# TrakerS_onecznyV3.net
KiCad netlist of a schematic drawn in EAGLE
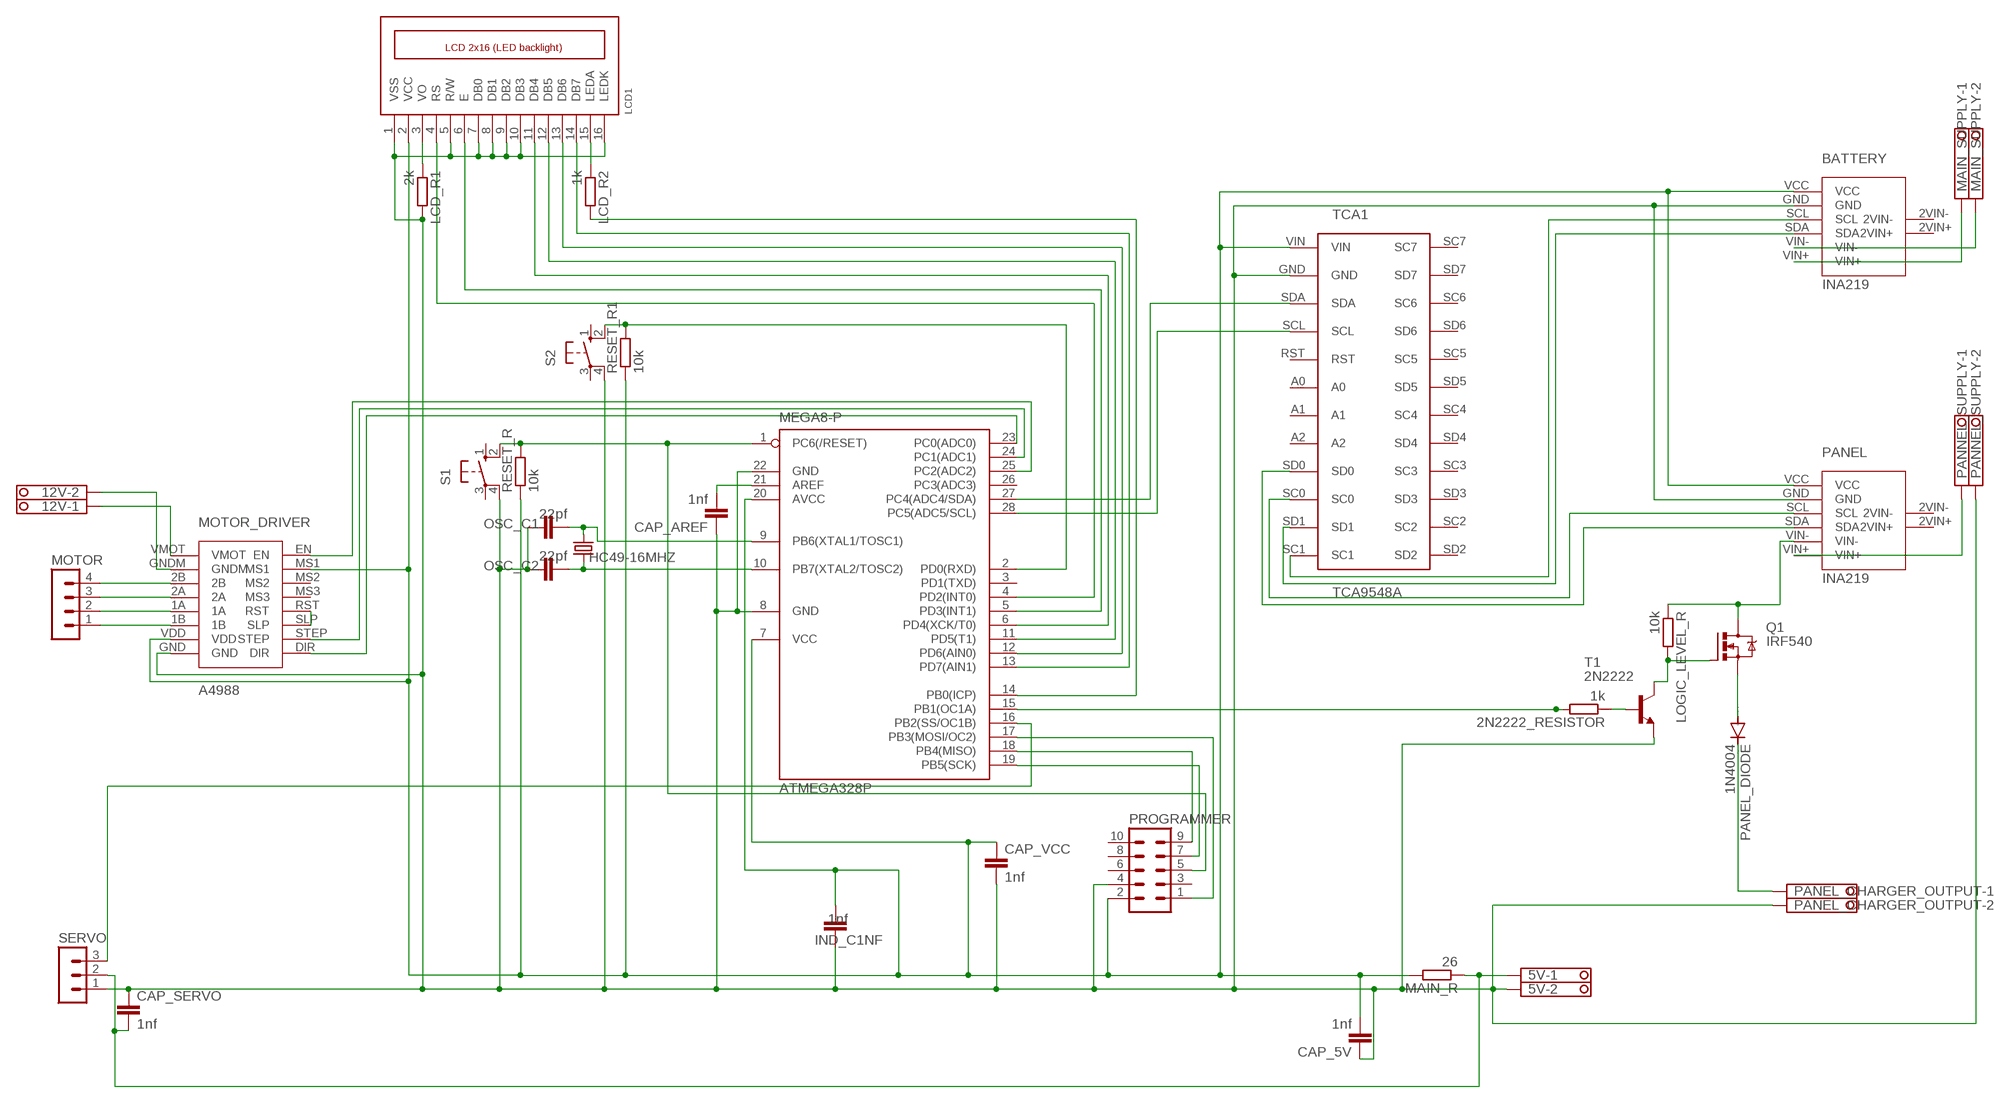
[diagram p0: schematic, sheet 1]

(export (version "E")
  (design (tool "Eeschema 10.0.6"))
  (components
    (comp (ref "2N2222_RESISTOR")
      (value "1k")
      (footprint "eagle-import:0207_2V")
      (libsource (lib "eagle-import") (part "R-EU_0207/2V"))
    )
    (comp (ref "5V")
      (value "TERMINAL-BLOCK-3.5MM-2-PIN-ROUND-PAD")
      (footprint "eagle-import:TERMINAL-BLOCK-2-PIN-3.5MM-ROUND-PAD")
      (libsource (lib "eagle-import") (part "TERMINAL-BLOCK-3.5MM-2-PIN-ROUND-PAD"))
    )
    (comp (ref "12V")
      (value "TERMINAL-BLOCK-3.5MM-2-PIN-ROUND-PAD")
      (footprint "eagle-import:TERMINAL-BLOCK-2-PIN-3.5MM-ROUND-PAD")
      (libsource (lib "eagle-import") (part "TERMINAL-BLOCK-3.5MM-2-PIN-ROUND-PAD"))
    )
    (comp (ref "ATMEGA328P")
      (value "MEGA8-P")
      (footprint "eagle-import:DIL28-3")
      (libsource (lib "eagle-import") (part "MEGA8-P"))
    )
    (comp (ref "BATTERY")
      (value "INA219")
      (footprint "eagle-import:INA219")
      (libsource (lib "eagle-import") (part "INA219"))
    )
    (comp (ref "CAP_5V")
      (value "1nf")
      (footprint "eagle-import:C025-024X044")
      (libsource (lib "eagle-import") (part "C-EU025-024X044"))
    )
    (comp (ref "CAP_AREF")
      (value "1nf")
      (footprint "eagle-import:C025-024X044")
      (libsource (lib "eagle-import") (part "C-EU025-024X044"))
    )
    (comp (ref "CAP_SERVO")
      (value "1nf")
      (footprint "eagle-import:C025-024X044")
      (libsource (lib "eagle-import") (part "C-EU025-024X044"))
    )
    (comp (ref "CAP_VCC")
      (value "1nf")
      (footprint "eagle-import:C025-024X044")
      (libsource (lib "eagle-import") (part "C-EU025-024X044"))
    )
    (comp (ref "HC49-16MHZ")
      (value "CRYTALHC49S")
      (footprint "eagle-import:HC49_S")
      (libsource (lib "eagle-import") (part "CRYTALHC49S"))
    )
    (comp (ref "IND_C1NF")
      (value "1nf")
      (footprint "eagle-import:C025-024X044")
      (libsource (lib "eagle-import") (part "C-EU025-024X044"))
    )
    (comp (ref "LCD1")
      (value "LCD_2X16_SIL")
      (footprint "eagle-import:HY-1602F")
      (libsource (lib "eagle-import") (part "LCD_2X16_SIL"))
    )
    (comp (ref "LCD_R1")
      (value "2k")
      (footprint "eagle-import:0207_2V")
      (libsource (lib "eagle-import") (part "R-EU_0207/2V"))
    )
    (comp (ref "LCD_R2")
      (value "1k")
      (footprint "eagle-import:0207_2V")
      (libsource (lib "eagle-import") (part "R-EU_0207/2V"))
    )
    (comp (ref "LOGIC_LEVEL_R")
      (value "10k")
      (footprint "eagle-import:0207_2V")
      (libsource (lib "eagle-import") (part "R-EU_0207/2V"))
    )
    (comp (ref "MAIN_R")
      (value "26")
      (footprint "eagle-import:0207_2V")
      (libsource (lib "eagle-import") (part "R-EU_0207/2V"))
    )
    (comp (ref "MAIN_SUPPLY")
      (value "TERMINAL-BLOCK-3.5MM-2-PIN-ROUND-PAD")
      (footprint "eagle-import:TERMINAL-BLOCK-2-PIN-3.5MM-ROUND-PAD")
      (libsource (lib "eagle-import") (part "TERMINAL-BLOCK-3.5MM-2-PIN-ROUND-PAD"))
    )
    (comp (ref "MOTOR")
      (value "MA04-1")
      (footprint "eagle-import:MA04-1")
      (libsource (lib "eagle-import") (part "MA04-1"))
    )
    (comp (ref "MOTOR_DRIVER")
      (value "A4988")
      (footprint "eagle-import:A4988")
      (libsource (lib "eagle-import") (part "A4988"))
    )
    (comp (ref "OSC_C1")
      (value "22pf")
      (footprint "eagle-import:C025-024X044")
      (libsource (lib "eagle-import") (part "C-EU025-024X044"))
    )
    (comp (ref "OSC_C2")
      (value "22pf")
      (footprint "eagle-import:C025-024X044")
      (libsource (lib "eagle-import") (part "C-EU025-024X044"))
    )
    (comp (ref "PANEL")
      (value "INA219")
      (footprint "eagle-import:INA219")
      (libsource (lib "eagle-import") (part "INA219"))
    )
    (comp (ref "PANEL_CHARGER_OUTPUT")
      (value "TERMINAL-BLOCK-3.5MM-2-PIN-ROUND-PAD")
      (footprint "eagle-import:TERMINAL-BLOCK-2-PIN-3.5MM-ROUND-PAD")
      (libsource (lib "eagle-import") (part "TERMINAL-BLOCK-3.5MM-2-PIN-ROUND-PAD"))
    )
    (comp (ref "PANEL_DIODE")
      (value "1N4004")
      (footprint "eagle-import:DO41-10")
      (libsource (lib "eagle-import") (part "1N4004"))
    )
    (comp (ref "PANNEL_SUPPLY")
      (value "TERMINAL-BLOCK-3.5MM-2-PIN-ROUND-PAD")
      (footprint "eagle-import:TERMINAL-BLOCK-2-PIN-3.5MM-ROUND-PAD")
      (libsource (lib "eagle-import") (part "TERMINAL-BLOCK-3.5MM-2-PIN-ROUND-PAD"))
    )
    (comp (ref "PROGRAMMER")
      (value "MA05-2")
      (footprint "eagle-import:MA05-2")
      (libsource (lib "eagle-import") (part "MA05-2"))
    )
    (comp (ref "Q1")
      (value "IRF540")
      (footprint "eagle-import:TO220BV")
      (libsource (lib "eagle-import") (part "IRF540"))
    )
    (comp (ref "RESET_R")
      (value "10k")
      (footprint "eagle-import:0207_2V")
      (libsource (lib "eagle-import") (part "R-EU_0207/2V"))
    )
    (comp (ref "RESET_R1")
      (value "10k")
      (footprint "eagle-import:0207_2V")
      (libsource (lib "eagle-import") (part "R-EU_0207/2V"))
    )
    (comp (ref "S1")
      (value "10-XX")
      (footprint "eagle-import:B3F-10XX")
      (fields (field (name "MPN") "B3F-1000"))
      (libsource (lib "eagle-import") (part "10-XX"))
    )
    (comp (ref "S2")
      (value "10-XX")
      (footprint "eagle-import:B3F-10XX")
      (fields (field (name "MPN") "B3F-1000"))
      (libsource (lib "eagle-import") (part "10-XX"))
    )
    (comp (ref "SERVO")
      (value "MA03-1")
      (footprint "eagle-import:MA03-1")
      (libsource (lib "eagle-import") (part "MA03-1"))
    )
    (comp (ref "T1")
      (value "2N2222")
      (footprint "eagle-import:TO92-EBC-OVAL")
      (libsource (lib "eagle-import") (part "2N2222"))
    )
    (comp (ref "TCA1")
      (value "TCA9548A")
      (footprint "eagle-import:TCA9548A")
      (libsource (lib "eagle-import") (part "TCA9548A"))
    )
  )
  (nets
    (net (code "1") (name "Net-(2N2222_RESISTOR-Pad1)") (class "Default")
      (node (ref "2N2222_RESISTOR") (pin "1") (pinfunction "1_1") (pintype "passive"))
      (node (ref "T1") (pin "B") (pinfunction "B_B") (pintype "passive"))
    )
    (net (code "2") (name "Net-(5VA-K)") (class "Default")
      (node (ref "5V") (pin "1") (pinfunction "K_1") (pintype "passive"))
      (node (ref "CAP_SERVO") (pin "2") (pinfunction "2_2") (pintype "passive"))
      (node (ref "MAIN_R") (pin "1") (pinfunction "1_1") (pintype "passive"))
      (node (ref "SERVO") (pin "2") (pinfunction "2_2") (pintype "passive"))
    )
    (net (code "3") (name "Net-(5VB-K)") (class "Default")
      (node (ref "5V") (pin "2") (pinfunction "K_2") (pintype "passive"))
      (node (ref "ATMEGA328P") (pin "22") (pinfunction "GND_22") (pintype "power_in"))
      (node (ref "ATMEGA328P") (pin "8") (pinfunction "GND_8") (pintype "power_in"))
      (node (ref "BATTERY") (pin "GND") (pinfunction "GND_GND") (pintype "bidirectional"))
      (node (ref "CAP_5V") (pin "1") (pinfunction "1_1") (pintype "passive"))
      (node (ref "CAP_AREF") (pin "1") (pinfunction "1_1") (pintype "passive"))
      (node (ref "CAP_SERVO") (pin "1") (pinfunction "1_1") (pintype "passive"))
      (node (ref "CAP_VCC") (pin "2") (pinfunction "2_2") (pintype "passive"))
      (node (ref "IND_C1NF") (pin "1") (pinfunction "1_1") (pintype "passive"))
      (node (ref "LCD1") (pin "1") (pinfunction "VSS_1") (pintype "power_in"))
      (node (ref "LCD1") (pin "10") (pinfunction "DB3_10") (pintype "bidirectional"))
      (node (ref "LCD1") (pin "16") (pinfunction "LEDK_16") (pintype "passive"))
      (node (ref "LCD1") (pin "5") (pinfunction "R/W_5") (pintype "input"))
      (node (ref "LCD1") (pin "7") (pinfunction "DB0_7") (pintype "bidirectional"))
      (node (ref "LCD1") (pin "8") (pinfunction "DB1_8") (pintype "bidirectional"))
      (node (ref "LCD1") (pin "9") (pinfunction "DB2_9") (pintype "bidirectional"))
      (node (ref "LCD_R1") (pin "2") (pinfunction "2_2") (pintype "passive"))
      (node (ref "MOTOR_DRIVER") (pin "GND") (pinfunction "GND_GND") (pintype "bidirectional"))
      (node (ref "OSC_C1") (pin "1") (pinfunction "1_1") (pintype "passive"))
      (node (ref "OSC_C2") (pin "1") (pinfunction "1_1") (pintype "passive"))
      (node (ref "PANEL") (pin "GND") (pinfunction "GND_GND") (pintype "bidirectional"))
      (node (ref "PANEL_CHARGER_OUTPUT") (pin "2") (pinfunction "K_2") (pintype "passive"))
      (node (ref "PANNEL_SUPPLY") (pin "2") (pinfunction "K_2") (pintype "passive"))
      (node (ref "PROGRAMMER") (pin "4") (pinfunction "4_4") (pintype "passive"))
      (node (ref "S1") (pin "4") (pinfunction "P1_4") (pintype "passive"))
      (node (ref "S2") (pin "4") (pinfunction "P1_4") (pintype "passive"))
      (node (ref "SERVO") (pin "1") (pinfunction "1_1") (pintype "passive"))
      (node (ref "T1") (pin "E") (pinfunction "E_E") (pintype "passive"))
      (node (ref "TCA1") (pin "GND") (pinfunction "GND_GND") (pintype "bidirectional"))
    )
    (net (code "4") (name "Net-(12VA-K)") (class "Default")
      (node (ref "12V") (pin "1") (pinfunction "K_1") (pintype "passive"))
      (node (ref "MOTOR_DRIVER") (pin "VMOT") (pinfunction "VMOT_VMOT") (pintype "bidirectional"))
    )
    (net (code "5") (name "Net-(12VB-K)") (class "Default")
      (node (ref "12V") (pin "2") (pinfunction "K_2") (pintype "passive"))
      (node (ref "MOTOR_DRIVER") (pin "GNDM") (pinfunction "GNDM_GNDM") (pintype "bidirectional"))
    )
    (net (code "6") (name "Net-(ATMEGA328P-AREF)") (class "Default")
      (node (ref "ATMEGA328P") (pin "21") (pinfunction "AREF_21") (pintype "passive"))
      (node (ref "CAP_AREF") (pin "2") (pinfunction "2_2") (pintype "passive"))
    )
    (net (code "7") (name "Net-(ATMEGA328P-AVCC)") (class "Default")
      (node (ref "ATMEGA328P") (pin "20") (pinfunction "AVCC_20") (pintype "power_in"))
      (node (ref "ATMEGA328P") (pin "7") (pinfunction "VCC_7") (pintype "power_in"))
      (node (ref "BATTERY") (pin "VCC") (pinfunction "VCC_VCC") (pintype "bidirectional"))
      (node (ref "CAP_5V") (pin "2") (pinfunction "2_2") (pintype "passive"))
      (node (ref "CAP_VCC") (pin "1") (pinfunction "1_1") (pintype "passive"))
      (node (ref "IND_C1NF") (pin "2") (pinfunction "2_2") (pintype "passive"))
      (node (ref "LCD1") (pin "2") (pinfunction "VCC_2") (pintype "power_in"))
      (node (ref "MAIN_R") (pin "2") (pinfunction "2_2") (pintype "passive"))
      (node (ref "MOTOR_DRIVER") (pin "MS1") (pinfunction "MS1_MS1") (pintype "bidirectional"))
      (node (ref "MOTOR_DRIVER") (pin "VDD") (pinfunction "VDD_VDD") (pintype "bidirectional"))
      (node (ref "PANEL") (pin "VCC") (pinfunction "VCC_VCC") (pintype "bidirectional"))
      (node (ref "PROGRAMMER") (pin "2") (pinfunction "2_2") (pintype "passive"))
      (node (ref "RESET_R") (pin "1") (pinfunction "1_1") (pintype "passive"))
      (node (ref "RESET_R1") (pin "1") (pinfunction "1_1") (pintype "passive"))
      (node (ref "TCA1") (pin "VIN") (pinfunction "VIN_VIN") (pintype "bidirectional"))
    )
    (net (code "8") (name "Net-(ATMEGA328P-PB0(ICP))") (class "Default")
      (node (ref "ATMEGA328P") (pin "14") (pinfunction "PB0(ICP)_14") (pintype "bidirectional"))
      (node (ref "LCD_R2") (pin "2") (pinfunction "2_2") (pintype "passive"))
    )
    (net (code "9") (name "Net-(ATMEGA328P-PB1(OC1A))") (class "Default")
      (node (ref "2N2222_RESISTOR") (pin "2") (pinfunction "2_2") (pintype "passive"))
      (node (ref "ATMEGA328P") (pin "15") (pinfunction "PB1(OC1A)_15") (pintype "bidirectional"))
    )
    (net (code "10") (name "Net-(ATMEGA328P-PB2(SS{slash}OC1B))") (class "Default")
      (node (ref "ATMEGA328P") (pin "16") (pinfunction "PB2(SS/OC1B)_16") (pintype "bidirectional"))
      (node (ref "SERVO") (pin "3") (pinfunction "3_3") (pintype "passive"))
    )
    (net (code "11") (name "Net-(ATMEGA328P-PB3(MOSI{slash}OC2))") (class "Default")
      (node (ref "ATMEGA328P") (pin "17") (pinfunction "PB3(MOSI/OC2)_17") (pintype "bidirectional"))
      (node (ref "PROGRAMMER") (pin "1") (pinfunction "1_1") (pintype "passive"))
    )
    (net (code "12") (name "Net-(ATMEGA328P-PB4(MISO))") (class "Default")
      (node (ref "ATMEGA328P") (pin "18") (pinfunction "PB4(MISO)_18") (pintype "bidirectional"))
      (node (ref "PROGRAMMER") (pin "9") (pinfunction "9_9") (pintype "passive"))
    )
    (net (code "13") (name "Net-(ATMEGA328P-PB5(SCK))") (class "Default")
      (node (ref "ATMEGA328P") (pin "19") (pinfunction "PB5(SCK)_19") (pintype "bidirectional"))
      (node (ref "PROGRAMMER") (pin "7") (pinfunction "7_7") (pintype "passive"))
    )
    (net (code "14") (name "Net-(ATMEGA328P-PB6(XTAL1{slash}TOSC1))") (class "Default")
      (node (ref "ATMEGA328P") (pin "9") (pinfunction "PB6(XTAL1/TOSC1)_9") (pintype "bidirectional"))
      (node (ref "HC49-16MHZ") (pin "1") (pinfunction "1_1") (pintype "passive"))
      (node (ref "OSC_C1") (pin "2") (pinfunction "2_2") (pintype "passive"))
    )
    (net (code "15") (name "Net-(ATMEGA328P-PB7(XTAL2{slash}TOSC2))") (class "Default")
      (node (ref "ATMEGA328P") (pin "10") (pinfunction "PB7(XTAL2/TOSC2)_10") (pintype "bidirectional"))
      (node (ref "HC49-16MHZ") (pin "2") (pinfunction "2_2") (pintype "passive"))
      (node (ref "OSC_C2") (pin "2") (pinfunction "2_2") (pintype "passive"))
    )
    (net (code "16") (name "Net-(ATMEGA328P-PC0(ADC0))") (class "Default")
      (node (ref "ATMEGA328P") (pin "23") (pinfunction "PC0(ADC0)_23") (pintype "bidirectional"))
      (node (ref "MOTOR_DRIVER") (pin "DIR") (pinfunction "DIR_DIR") (pintype "bidirectional"))
    )
    (net (code "17") (name "Net-(ATMEGA328P-PC1(ADC1))") (class "Default")
      (node (ref "ATMEGA328P") (pin "24") (pinfunction "PC1(ADC1)_24") (pintype "bidirectional"))
      (node (ref "MOTOR_DRIVER") (pin "STEP") (pinfunction "STEP_STEP") (pintype "bidirectional"))
    )
    (net (code "18") (name "Net-(ATMEGA328P-PC2(ADC2))") (class "Default")
      (node (ref "ATMEGA328P") (pin "25") (pinfunction "PC2(ADC2)_25") (pintype "bidirectional"))
      (node (ref "MOTOR_DRIVER") (pin "EN") (pinfunction "EN_EN") (pintype "bidirectional"))
    )
    (net (code "19") (name "Net-(ATMEGA328P-PC4(ADC4{slash}SDA))") (class "Default")
      (node (ref "ATMEGA328P") (pin "27") (pinfunction "PC4(ADC4/SDA)_27") (pintype "bidirectional"))
      (node (ref "TCA1") (pin "SDA") (pinfunction "SDA_SDA") (pintype "bidirectional"))
    )
    (net (code "20") (name "Net-(ATMEGA328P-PC5(ADC5{slash}SCL))") (class "Default")
      (node (ref "ATMEGA328P") (pin "28") (pinfunction "PC5(ADC5/SCL)_28") (pintype "bidirectional"))
      (node (ref "TCA1") (pin "SCL") (pinfunction "SCL_SCL") (pintype "bidirectional"))
    )
    (net (code "21") (name "Net-(ATMEGA328P-PC6({slash}RESET))") (class "Default")
      (node (ref "ATMEGA328P") (pin "1") (pinfunction "PC6(/RESET)_1") (pintype "bidirectional"))
      (node (ref "PROGRAMMER") (pin "5") (pinfunction "5_5") (pintype "passive"))
      (node (ref "RESET_R") (pin "2") (pinfunction "2_2") (pintype "passive"))
      (node (ref "S1") (pin "2") (pinfunction "S1_2") (pintype "passive"))
    )
    (net (code "22") (name "Net-(ATMEGA328P-PD0(RXD))") (class "Default")
      (node (ref "ATMEGA328P") (pin "2") (pinfunction "PD0(RXD)_2") (pintype "bidirectional"))
      (node (ref "RESET_R1") (pin "2") (pinfunction "2_2") (pintype "passive"))
      (node (ref "S2") (pin "2") (pinfunction "S1_2") (pintype "passive"))
    )
    (net (code "23") (name "Net-(ATMEGA328P-PD2(INT0))") (class "Default")
      (node (ref "ATMEGA328P") (pin "4") (pinfunction "PD2(INT0)_4") (pintype "bidirectional"))
      (node (ref "LCD1") (pin "4") (pinfunction "RS_4") (pintype "input"))
    )
    (net (code "24") (name "Net-(ATMEGA328P-PD3(INT1))") (class "Default")
      (node (ref "ATMEGA328P") (pin "5") (pinfunction "PD3(INT1)_5") (pintype "bidirectional"))
      (node (ref "LCD1") (pin "6") (pinfunction "E_6") (pintype "input"))
    )
    (net (code "25") (name "Net-(ATMEGA328P-PD4(XCK{slash}T0))") (class "Default")
      (node (ref "ATMEGA328P") (pin "6") (pinfunction "PD4(XCK/T0)_6") (pintype "bidirectional"))
      (node (ref "LCD1") (pin "11") (pinfunction "DB4_11") (pintype "bidirectional"))
    )
    (net (code "26") (name "Net-(ATMEGA328P-PD5(T1))") (class "Default")
      (node (ref "ATMEGA328P") (pin "11") (pinfunction "PD5(T1)_11") (pintype "bidirectional"))
      (node (ref "LCD1") (pin "12") (pinfunction "DB5_12") (pintype "bidirectional"))
    )
    (net (code "27") (name "Net-(ATMEGA328P-PD6(AIN0))") (class "Default")
      (node (ref "ATMEGA328P") (pin "12") (pinfunction "PD6(AIN0)_12") (pintype "bidirectional"))
      (node (ref "LCD1") (pin "13") (pinfunction "DB6_13") (pintype "bidirectional"))
    )
    (net (code "28") (name "Net-(ATMEGA328P-PD7(AIN1))") (class "Default")
      (node (ref "ATMEGA328P") (pin "13") (pinfunction "PD7(AIN1)_13") (pintype "bidirectional"))
      (node (ref "LCD1") (pin "14") (pinfunction "DB7_14") (pintype "bidirectional"))
    )
    (net (code "29") (name "Net-(BATTERY-PadSCL)") (class "Default")
      (node (ref "BATTERY") (pin "SCL") (pinfunction "SCL_SCL") (pintype "bidirectional"))
      (node (ref "TCA1") (pin "SC1") (pinfunction "SC1_SC1") (pintype "bidirectional"))
    )
    (net (code "30") (name "Net-(BATTERY-PadSDA)") (class "Default")
      (node (ref "BATTERY") (pin "SDA") (pinfunction "SDA_SDA") (pintype "bidirectional"))
      (node (ref "TCA1") (pin "SD1") (pinfunction "SD1_SD1") (pintype "bidirectional"))
    )
    (net (code "31") (name "Net-(LCD1-LEDA)") (class "Default")
      (node (ref "LCD1") (pin "15") (pinfunction "LEDA_15") (pintype "passive"))
      (node (ref "LCD_R2") (pin "1") (pinfunction "1_1") (pintype "passive"))
    )
    (net (code "32") (name "Net-(LCD1-VO)") (class "Default")
      (node (ref "LCD1") (pin "3") (pinfunction "VO_3") (pintype "input"))
      (node (ref "LCD_R1") (pin "1") (pinfunction "1_1") (pintype "passive"))
    )
    (net (code "33") (name "Net-(LOGIC_LEVEL_R-Pad1)") (class "Default")
      (node (ref "LOGIC_LEVEL_R") (pin "1") (pinfunction "1_1") (pintype "passive"))
      (node (ref "PANEL") (pin "VIN-") (pinfunction "VIN-_VIN-") (pintype "bidirectional"))
      (node (ref "Q1") (pin "D") (pinfunction "D_D") (pintype "passive"))
    )
    (net (code "34") (name "Net-(LOGIC_LEVEL_R-Pad2)") (class "Default")
      (node (ref "LOGIC_LEVEL_R") (pin "2") (pinfunction "2_2") (pintype "passive"))
      (node (ref "Q1") (pin "G") (pinfunction "G_G") (pintype "passive"))
      (node (ref "T1") (pin "C") (pinfunction "C_C") (pintype "passive"))
    )
    (net (code "35") (name "Net-(MAIN_SUPPLYA-K)") (class "Default")
      (node (ref "BATTERY") (pin "VIN+") (pinfunction "VIN+_VIN+") (pintype "bidirectional"))
      (node (ref "MAIN_SUPPLY") (pin "1") (pinfunction "K_1") (pintype "passive"))
    )
    (net (code "36") (name "Net-(MAIN_SUPPLYB-K)") (class "Default")
      (node (ref "BATTERY") (pin "VIN-") (pinfunction "VIN-_VIN-") (pintype "bidirectional"))
      (node (ref "MAIN_SUPPLY") (pin "2") (pinfunction "K_2") (pintype "passive"))
    )
    (net (code "37") (name "Net-(MOTOR-Pad1)") (class "Default")
      (node (ref "MOTOR") (pin "1") (pinfunction "1_1") (pintype "passive"))
      (node (ref "MOTOR_DRIVER") (pin "1B") (pinfunction "1B_1B") (pintype "bidirectional"))
    )
    (net (code "38") (name "Net-(MOTOR-Pad2)") (class "Default")
      (node (ref "MOTOR") (pin "2") (pinfunction "2_2") (pintype "passive"))
      (node (ref "MOTOR_DRIVER") (pin "1A") (pinfunction "1A_1A") (pintype "bidirectional"))
    )
    (net (code "39") (name "Net-(MOTOR-Pad3)") (class "Default")
      (node (ref "MOTOR") (pin "3") (pinfunction "3_3") (pintype "passive"))
      (node (ref "MOTOR_DRIVER") (pin "2A") (pinfunction "2A_2A") (pintype "bidirectional"))
    )
    (net (code "40") (name "Net-(MOTOR-Pad4)") (class "Default")
      (node (ref "MOTOR") (pin "4") (pinfunction "4_4") (pintype "passive"))
      (node (ref "MOTOR_DRIVER") (pin "2B") (pinfunction "2B_2B") (pintype "bidirectional"))
    )
    (net (code "41") (name "Net-(MOTOR_DRIVER-PadRST)") (class "Default")
      (node (ref "MOTOR_DRIVER") (pin "RST") (pinfunction "RST_RST") (pintype "bidirectional"))
      (node (ref "MOTOR_DRIVER") (pin "SLP") (pinfunction "SLP_SLP") (pintype "bidirectional"))
    )
    (net (code "42") (name "Net-(PANEL-PadSCL)") (class "Default")
      (node (ref "PANEL") (pin "SCL") (pinfunction "SCL_SCL") (pintype "bidirectional"))
      (node (ref "TCA1") (pin "SC0") (pinfunction "SC0_SC0") (pintype "bidirectional"))
    )
    (net (code "43") (name "Net-(PANEL-PadSDA)") (class "Default")
      (node (ref "PANEL") (pin "SDA") (pinfunction "SDA_SDA") (pintype "bidirectional"))
      (node (ref "TCA1") (pin "SD0") (pinfunction "SD0_SD0") (pintype "bidirectional"))
    )
    (net (code "44") (name "Net-(PANEL_CHARGER_OUTPUTA-K)") (class "Default")
      (node (ref "PANEL_CHARGER_OUTPUT") (pin "1") (pinfunction "K_1") (pintype "passive"))
      (node (ref "PANEL_DIODE") (pin "C") (pinfunction "C_C") (pintype "passive"))
    )
    (net (code "45") (name "Net-(PANEL_DIODE-PadA)") (class "Default")
      (node (ref "PANEL_DIODE") (pin "A") (pinfunction "A_A") (pintype "passive"))
      (node (ref "Q1") (pin "S") (pinfunction "S_S") (pintype "passive"))
    )
    (net (code "46") (name "Net-(PANNEL_SUPPLYA-K)") (class "Default")
      (node (ref "PANEL") (pin "VIN+") (pinfunction "VIN+_VIN+") (pintype "bidirectional"))
      (node (ref "PANNEL_SUPPLY") (pin "1") (pinfunction "K_1") (pintype "passive"))
    )
    (net (code "47") (name "unconnected-(ATMEGA328P-PC3(ADC3)-Pad26)") (class "Default")
      (node (ref "ATMEGA328P") (pin "26") (pinfunction "PC3(ADC3)_26") (pintype "bidirectional"))
    )
    (net (code "48") (name "unconnected-(ATMEGA328P-PD1(TXD)-Pad3)") (class "Default")
      (node (ref "ATMEGA328P") (pin "3") (pinfunction "PD1(TXD)_3") (pintype "bidirectional"))
    )
    (net (code "49") (name "unconnected-(BATTERY-Pad2VIN+)") (class "Default")
      (node (ref "BATTERY") (pin "2VIN+") (pinfunction "2VIN+_2VIN+") (pintype "bidirectional"))
    )
    (net (code "50") (name "unconnected-(BATTERY-Pad2VIN-)") (class "Default")
      (node (ref "BATTERY") (pin "2VIN-") (pinfunction "2VIN-_2VIN-") (pintype "bidirectional"))
    )
    (net (code "51") (name "unconnected-(MOTOR_DRIVER-PadMS2)") (class "Default")
      (node (ref "MOTOR_DRIVER") (pin "MS2") (pinfunction "MS2_MS2") (pintype "bidirectional"))
    )
    (net (code "52") (name "unconnected-(MOTOR_DRIVER-PadMS3)") (class "Default")
      (node (ref "MOTOR_DRIVER") (pin "MS3") (pinfunction "MS3_MS3") (pintype "bidirectional"))
    )
    (net (code "53") (name "unconnected-(PANEL-Pad2VIN+)") (class "Default")
      (node (ref "PANEL") (pin "2VIN+") (pinfunction "2VIN+_2VIN+") (pintype "bidirectional"))
    )
    (net (code "54") (name "unconnected-(PANEL-Pad2VIN-)") (class "Default")
      (node (ref "PANEL") (pin "2VIN-") (pinfunction "2VIN-_2VIN-") (pintype "bidirectional"))
    )
    (net (code "55") (name "unconnected-(PROGRAMMER-Pad3)") (class "Default")
      (node (ref "PROGRAMMER") (pin "3") (pinfunction "3_3") (pintype "passive"))
    )
    (net (code "56") (name "unconnected-(PROGRAMMER-Pad6)") (class "Default")
      (node (ref "PROGRAMMER") (pin "6") (pinfunction "6_6") (pintype "passive"))
    )
    (net (code "57") (name "unconnected-(PROGRAMMER-Pad8)") (class "Default")
      (node (ref "PROGRAMMER") (pin "8") (pinfunction "8_8") (pintype "passive"))
    )
    (net (code "58") (name "unconnected-(PROGRAMMER-Pad10)") (class "Default")
      (node (ref "PROGRAMMER") (pin "10") (pinfunction "10_10") (pintype "passive"))
    )
    (net (code "59") (name "unconnected-(S1-P-Pad3)") (class "Default")
      (node (ref "S1") (pin "3") (pinfunction "P_3") (pintype "passive"))
    )
    (net (code "60") (name "unconnected-(S1-S-Pad1)") (class "Default")
      (node (ref "S1") (pin "1") (pinfunction "S_1") (pintype "passive"))
    )
    (net (code "61") (name "unconnected-(S2-P-Pad3)") (class "Default")
      (node (ref "S2") (pin "3") (pinfunction "P_3") (pintype "passive"))
    )
    (net (code "62") (name "unconnected-(S2-S-Pad1)") (class "Default")
      (node (ref "S2") (pin "1") (pinfunction "S_1") (pintype "passive"))
    )
    (net (code "63") (name "unconnected-(TCA1-PadA0)") (class "Default")
      (node (ref "TCA1") (pin "A0") (pinfunction "A0_A0") (pintype "bidirectional"))
    )
    (net (code "64") (name "unconnected-(TCA1-PadA1)") (class "Default")
      (node (ref "TCA1") (pin "A1") (pinfunction "A1_A1") (pintype "bidirectional"))
    )
    (net (code "65") (name "unconnected-(TCA1-PadA2)") (class "Default")
      (node (ref "TCA1") (pin "A2") (pinfunction "A2_A2") (pintype "bidirectional"))
    )
    (net (code "66") (name "unconnected-(TCA1-PadRST)") (class "Default")
      (node (ref "TCA1") (pin "RST") (pinfunction "RST_RST") (pintype "bidirectional"))
    )
    (net (code "67") (name "unconnected-(TCA1-PadSC2)") (class "Default")
      (node (ref "TCA1") (pin "SC2") (pinfunction "SC2_SC2") (pintype "bidirectional"))
    )
    (net (code "68") (name "unconnected-(TCA1-PadSC3)") (class "Default")
      (node (ref "TCA1") (pin "SC3") (pinfunction "SC3_SC3") (pintype "bidirectional"))
    )
    (net (code "69") (name "unconnected-(TCA1-PadSC4)") (class "Default")
      (node (ref "TCA1") (pin "SC4") (pinfunction "SC4_SC4") (pintype "bidirectional"))
    )
    (net (code "70") (name "unconnected-(TCA1-PadSC5)") (class "Default")
      (node (ref "TCA1") (pin "SC5") (pinfunction "SC5_SC5") (pintype "bidirectional"))
    )
    (net (code "71") (name "unconnected-(TCA1-PadSC6)") (class "Default")
      (node (ref "TCA1") (pin "SC6") (pinfunction "SC6_SC6") (pintype "bidirectional"))
    )
    (net (code "72") (name "unconnected-(TCA1-PadSC7)") (class "Default")
      (node (ref "TCA1") (pin "SC7") (pinfunction "SC7_SC7") (pintype "bidirectional"))
    )
    (net (code "73") (name "unconnected-(TCA1-PadSD2)") (class "Default")
      (node (ref "TCA1") (pin "SD2") (pinfunction "SD2_SD2") (pintype "bidirectional"))
    )
    (net (code "74") (name "unconnected-(TCA1-PadSD3)") (class "Default")
      (node (ref "TCA1") (pin "SD3") (pinfunction "SD3_SD3") (pintype "bidirectional"))
    )
    (net (code "75") (name "unconnected-(TCA1-PadSD4)") (class "Default")
      (node (ref "TCA1") (pin "SD4") (pinfunction "SD4_SD4") (pintype "bidirectional"))
    )
    (net (code "76") (name "unconnected-(TCA1-PadSD5)") (class "Default")
      (node (ref "TCA1") (pin "SD5") (pinfunction "SD5_SD5") (pintype "bidirectional"))
    )
    (net (code "77") (name "unconnected-(TCA1-PadSD6)") (class "Default")
      (node (ref "TCA1") (pin "SD6") (pinfunction "SD6_SD6") (pintype "bidirectional"))
    )
    (net (code "78") (name "unconnected-(TCA1-PadSD7)") (class "Default")
      (node (ref "TCA1") (pin "SD7") (pinfunction "SD7_SD7") (pintype "bidirectional"))
    )
  )
)
